# v10_microUSB.net
KiCad netlist of a schematic drawn in EAGLE
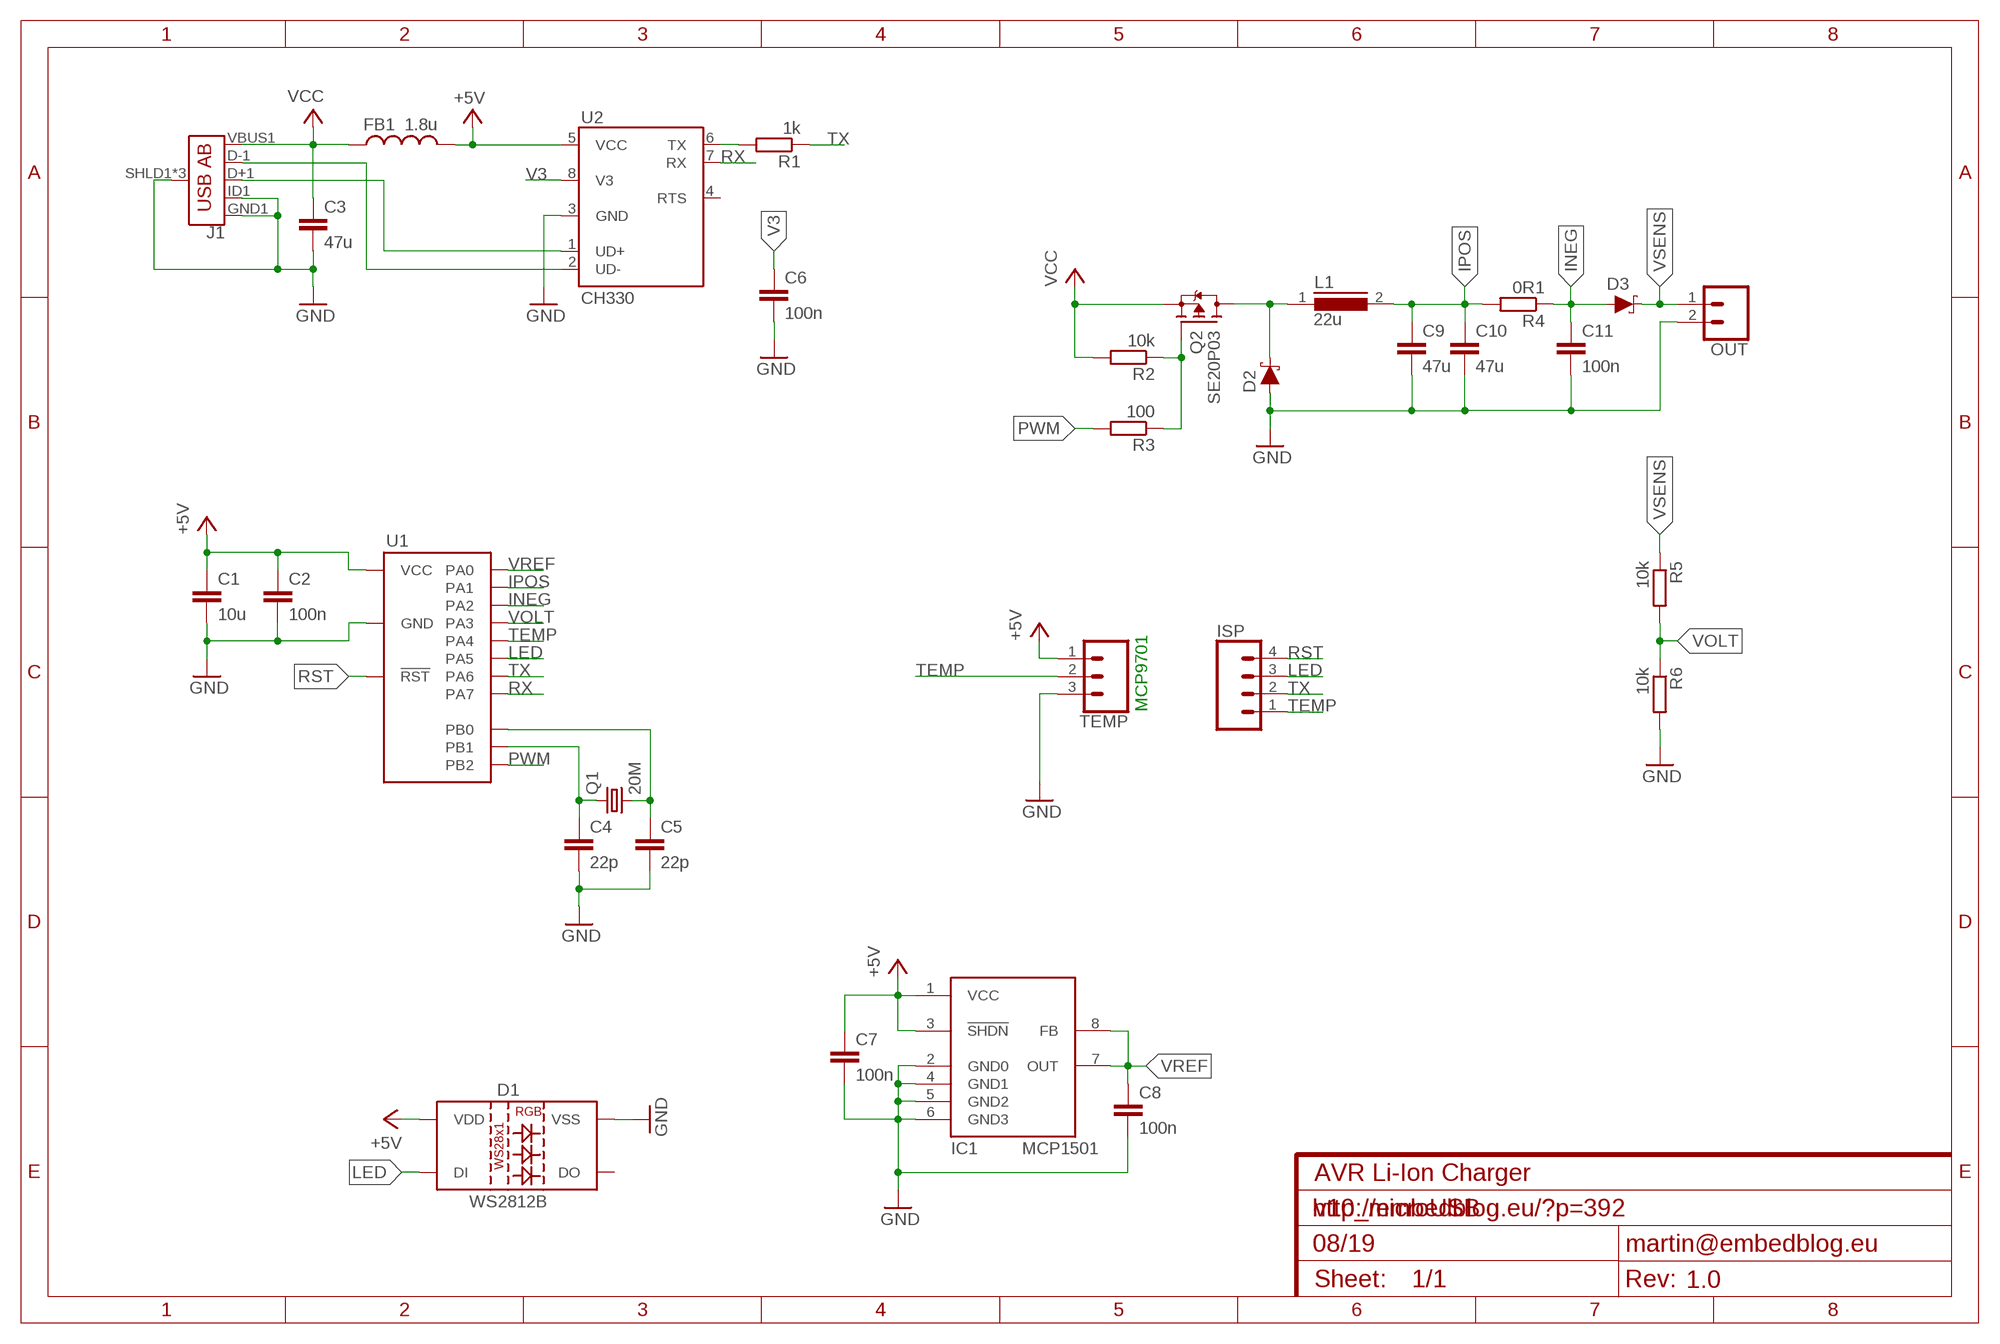
[diagram p0: schematic, sheet 1]

(export (version "E")
  (design (tool "Eeschema 10.0.6"))
  (components
    (comp (ref "C1")
      (value "10u")
      (footprint "eagle-import:C0805")
      (libsource (lib "eagle-import") (part "C-EUC0805"))
    )
    (comp (ref "C2")
      (value "100n")
      (footprint "eagle-import:C0805")
      (libsource (lib "eagle-import") (part "C-EUC0805"))
    )
    (comp (ref "C3")
      (value "47u")
      (footprint "eagle-import:C1206")
      (libsource (lib "eagle-import") (part "C-EUC1206"))
    )
    (comp (ref "C4")
      (value "22p")
      (footprint "eagle-import:C0805")
      (libsource (lib "eagle-import") (part "C-EUC0805"))
    )
    (comp (ref "C5")
      (value "22p")
      (footprint "eagle-import:C0805")
      (libsource (lib "eagle-import") (part "C-EUC0805"))
    )
    (comp (ref "C6")
      (value "100n")
      (footprint "eagle-import:C0805")
      (libsource (lib "eagle-import") (part "C-EUC0805"))
    )
    (comp (ref "C7")
      (value "100n")
      (footprint "eagle-import:C0805")
      (libsource (lib "eagle-import") (part "C-EUC0805"))
    )
    (comp (ref "C8")
      (value "100n")
      (footprint "eagle-import:C0805")
      (libsource (lib "eagle-import") (part "C-EUC0805"))
    )
    (comp (ref "C9")
      (value "47u")
      (footprint "eagle-import:C1206")
      (libsource (lib "eagle-import") (part "C-EUC1206"))
    )
    (comp (ref "C10")
      (value "47u")
      (footprint "eagle-import:C1206")
      (libsource (lib "eagle-import") (part "C-EUC1206"))
    )
    (comp (ref "C11")
      (value "100n")
      (footprint "eagle-import:C0805")
      (libsource (lib "eagle-import") (part "C-EUC0805"))
    )
    (comp (ref "D1")
      (value "WS2812B")
      (footprint "eagle-import:WS2812B")
      (libsource (lib "eagle-import") (part "WS2812B"))
    )
    (comp (ref "D2")
      (value "3A/40V/500mV")
      (footprint "eagle-import:SMA-DIODE")
      (libsource (lib "eagle-import") (part "DIODE-SCHOTTKY-B340A"))
    )
    (comp (ref "D3")
      (value "3A/40V/500mV")
      (footprint "eagle-import:SMA-DIODE")
      (libsource (lib "eagle-import") (part "DIODE-SCHOTTKY-B340A"))
    )
    (comp (ref "FB1")
      (value "1.8u")
      (footprint "eagle-import:1206")
      (libsource (lib "eagle-import") (part "FERRITE-BEADC"))
    )
    (comp (ref "IC1")
      (value "MCP1501")
      (footprint "eagle-import:SO08")
      (libsource (lib "eagle-import") (part "MCP1501"))
    )
    (comp (ref "ISP")
      (value "CONN_04")
      (footprint "eagle-import:1X04")
      (libsource (lib "eagle-import") (part "CONN_04"))
    )
    (comp (ref "J1")
      (value "USB_AB_SMT")
      (footprint "eagle-import:USB-AB-MICRO-SMD")
      (libsource (lib "eagle-import") (part "USB_AB_SMT"))
    )
    (comp (ref "L1")
      (value "22u")
      (footprint "eagle-import:DR73")
      (libsource (lib "eagle-import") (part "DR73"))
    )
    (comp (ref "OUT")
      (value "CONN_02PTH3")
      (footprint "eagle-import:1X02_LONGPADS")
      (libsource (lib "eagle-import") (part "CONN_02PTH3"))
    )
    (comp (ref "Q1")
      (value "20M")
      (footprint "eagle-import:HC49_S")
      (libsource (lib "eagle-import") (part "CRYSTALHC49S"))
    )
    (comp (ref "Q2")
      (value "SE20P03")
      (footprint "eagle-import:TO252")
      (libsource (lib "eagle-import") (part "FDD4141TO252"))
    )
    (comp (ref "R1")
      (value "1k")
      (footprint "eagle-import:R0805")
      (libsource (lib "eagle-import") (part "R-EU_R0805"))
    )
    (comp (ref "R2")
      (value "10k")
      (footprint "eagle-import:R0805")
      (libsource (lib "eagle-import") (part "R-EU_R0805"))
    )
    (comp (ref "R3")
      (value "100")
      (footprint "eagle-import:R0805")
      (libsource (lib "eagle-import") (part "R-EU_R0805"))
    )
    (comp (ref "R4")
      (value "0R1")
      (footprint "eagle-import:R1206")
      (libsource (lib "eagle-import") (part "R-EU_R1206"))
    )
    (comp (ref "R5")
      (value "10k")
      (footprint "eagle-import:R0805")
      (libsource (lib "eagle-import") (part "R-EU_R0805"))
    )
    (comp (ref "R6")
      (value "10k")
      (footprint "eagle-import:R0805")
      (libsource (lib "eagle-import") (part "R-EU_R0805"))
    )
    (comp (ref "TEMP")
      (value "455-1750-1-ND")
      (footprint "eagle-import:1X03")
      (libsource (lib "eagle-import") (part "CONN_03"))
    )
    (comp (ref "U1")
      (value "ATTINY24")
      (footprint "eagle-import:SO014")
      (libsource (lib "eagle-import") (part "ATTINY24"))
    )
    (comp (ref "U2")
      (value "CH330")
      (footprint "eagle-import:SO08")
      (libsource (lib "eagle-import") (part "CH330"))
    )
  )
  (nets
    (net (code "1") (name "+5V") (class "Default")
      (node (ref "C1") (pin "1") (pinfunction "1_1") (pintype "passive"))
      (node (ref "C2") (pin "1") (pinfunction "1_1") (pintype "passive"))
      (node (ref "C7") (pin "1") (pinfunction "1_1") (pintype "passive"))
      (node (ref "D1") (pin "1") (pinfunction "VDD_1") (pintype "bidirectional"))
      (node (ref "FB1") (pin "2") (pinfunction "2_2") (pintype "passive"))
      (node (ref "IC1") (pin "1") (pinfunction "VCC_1") (pintype "bidirectional"))
      (node (ref "IC1") (pin "3") (pinfunction "~{SHDN}_3") (pintype "bidirectional"))
      (node (ref "TEMP") (pin "1") (pinfunction "1_1") (pintype "passive"))
      (node (ref "U1") (pin "1") (pinfunction "VCC_1") (pintype "bidirectional"))
      (node (ref "U2") (pin "5") (pinfunction "VCC_5") (pintype "bidirectional"))
    )
    (net (code "2") (name "/RX") (class "Default")
      (node (ref "U1") (pin "6") (pinfunction "PA7_6") (pintype "bidirectional"))
      (node (ref "U2") (pin "7") (pinfunction "RX_7") (pintype "bidirectional"))
    )
    (net (code "3") (name "/TEMP") (class "Default")
      (node (ref "ISP") (pin "1") (pinfunction "1_1") (pintype "passive"))
      (node (ref "TEMP") (pin "2") (pinfunction "2_2") (pintype "passive"))
      (node (ref "U1") (pin "9") (pinfunction "PA4_9") (pintype "bidirectional"))
    )
    (net (code "4") (name "/TX") (class "Default")
      (node (ref "ISP") (pin "2") (pinfunction "2_2") (pintype "passive"))
      (node (ref "R1") (pin "1") (pinfunction "1_1") (pintype "passive"))
      (node (ref "U1") (pin "7") (pinfunction "PA6_7") (pintype "bidirectional"))
    )
    (net (code "5") (name "GND") (class "Default")
      (node (ref "C1") (pin "2") (pinfunction "2_2") (pintype "passive"))
      (node (ref "C10") (pin "2") (pinfunction "2_2") (pintype "passive"))
      (node (ref "C11") (pin "2") (pinfunction "2_2") (pintype "passive"))
      (node (ref "C2") (pin "2") (pinfunction "2_2") (pintype "passive"))
      (node (ref "C3") (pin "2") (pinfunction "2_2") (pintype "passive"))
      (node (ref "C4") (pin "2") (pinfunction "2_2") (pintype "passive"))
      (node (ref "C5") (pin "2") (pinfunction "2_2") (pintype "passive"))
      (node (ref "C6") (pin "2") (pinfunction "2_2") (pintype "passive"))
      (node (ref "C7") (pin "2") (pinfunction "2_2") (pintype "passive"))
      (node (ref "C8") (pin "2") (pinfunction "2_2") (pintype "passive"))
      (node (ref "C9") (pin "2") (pinfunction "2_2") (pintype "passive"))
      (node (ref "D1") (pin "3") (pinfunction "VSS_3") (pintype "bidirectional"))
      (node (ref "D2") (pin "A") (pinfunction "A_A") (pintype "passive"))
      (node (ref "IC1") (pin "2") (pinfunction "GND0_2") (pintype "bidirectional"))
      (node (ref "IC1") (pin "4") (pinfunction "GND1_4") (pintype "bidirectional"))
      (node (ref "IC1") (pin "5") (pinfunction "GND2_5") (pintype "bidirectional"))
      (node (ref "IC1") (pin "6") (pinfunction "GND3_6") (pintype "bidirectional"))
      (node (ref "J1") (pin "GND1") (pinfunction "GND_GND1") (pintype "power_in"))
      (node (ref "J1") (pin "ID1") (pinfunction "USBID_ID1") (pintype "bidirectional"))
      (node (ref "J1") (pin "SHLD1") (pinfunction "SHIELD_SHLD1") (pintype "bidirectional"))
      (node (ref "J1") (pin "SHLD2") (pinfunction "SHIELD_SHLD2") (pintype "bidirectional"))
      (node (ref "J1") (pin "SHLD3") (pinfunction "SHIELD_SHLD3") (pintype "bidirectional"))
      (node (ref "OUT") (pin "2") (pinfunction "2_2") (pintype "passive"))
      (node (ref "R6") (pin "2") (pinfunction "2_2") (pintype "passive"))
      (node (ref "TEMP") (pin "3") (pinfunction "3_3") (pintype "passive"))
      (node (ref "U1") (pin "14") (pinfunction "GND_14") (pintype "bidirectional"))
      (node (ref "U2") (pin "3") (pinfunction "GND_3") (pintype "bidirectional"))
    )
    (net (code "6") (name "INEG") (class "Default")
      (node (ref "C11") (pin "1") (pinfunction "1_1") (pintype "passive"))
      (node (ref "D3") (pin "A") (pinfunction "A_A") (pintype "passive"))
      (node (ref "R4") (pin "1") (pinfunction "1_1") (pintype "passive"))
      (node (ref "U1") (pin "11") (pinfunction "PA2_11") (pintype "bidirectional"))
    )
    (net (code "7") (name "IPOS") (class "Default")
      (node (ref "C10") (pin "1") (pinfunction "1_1") (pintype "passive"))
      (node (ref "C9") (pin "1") (pinfunction "1_1") (pintype "passive"))
      (node (ref "L1") (pin "2") (pinfunction "2_2") (pintype "passive"))
      (node (ref "R4") (pin "2") (pinfunction "2_2") (pintype "passive"))
      (node (ref "U1") (pin "12") (pinfunction "PA1_12") (pintype "bidirectional"))
    )
    (net (code "8") (name "LED") (class "Default")
      (node (ref "D1") (pin "4") (pinfunction "DI_4") (pintype "bidirectional"))
      (node (ref "ISP") (pin "3") (pinfunction "3_3") (pintype "passive"))
      (node (ref "U1") (pin "8") (pinfunction "PA5_8") (pintype "bidirectional"))
    )
    (net (code "9") (name "Net-(J1-D+)") (class "Default")
      (node (ref "J1") (pin "D+1") (pinfunction "D+_D+1") (pintype "bidirectional"))
      (node (ref "U2") (pin "1") (pinfunction "UD+_1") (pintype "bidirectional"))
    )
    (net (code "10") (name "Net-(J1-D-)") (class "Default")
      (node (ref "J1") (pin "D-1") (pinfunction "D-_D-1") (pintype "bidirectional"))
      (node (ref "U2") (pin "2") (pinfunction "UD-_2") (pintype "bidirectional"))
    )
    (net (code "11") (name "Net-(Q2-D)") (class "Default")
      (node (ref "D2") (pin "C") (pinfunction "C_C") (pintype "passive"))
      (node (ref "L1") (pin "1") (pinfunction "1_1") (pintype "passive"))
      (node (ref "Q2") (pin "3") (pinfunction "D_3") (pintype "passive"))
    )
    (net (code "12") (name "Net-(Q2-G)") (class "Default")
      (node (ref "Q2") (pin "1") (pinfunction "G_1") (pintype "passive"))
      (node (ref "R2") (pin "1") (pinfunction "1_1") (pintype "passive"))
      (node (ref "R3") (pin "1") (pinfunction "1_1") (pintype "passive"))
    )
    (net (code "13") (name "Net-(U1-PB0)") (class "Default")
      (node (ref "C5") (pin "1") (pinfunction "1_1") (pintype "passive"))
      (node (ref "Q1") (pin "2") (pinfunction "2_2") (pintype "passive"))
      (node (ref "U1") (pin "2") (pinfunction "PB0_2") (pintype "bidirectional"))
    )
    (net (code "14") (name "Net-(U1-PB1)") (class "Default")
      (node (ref "C4") (pin "1") (pinfunction "1_1") (pintype "passive"))
      (node (ref "Q1") (pin "1") (pinfunction "1_1") (pintype "passive"))
      (node (ref "U1") (pin "3") (pinfunction "PB1_3") (pintype "bidirectional"))
    )
    (net (code "15") (name "Net-(U2-TX)") (class "Default")
      (node (ref "R1") (pin "2") (pinfunction "2_2") (pintype "passive"))
      (node (ref "U2") (pin "6") (pinfunction "TX_6") (pintype "bidirectional"))
    )
    (net (code "16") (name "PWM") (class "Default")
      (node (ref "R3") (pin "2") (pinfunction "2_2") (pintype "passive"))
      (node (ref "U1") (pin "5") (pinfunction "PB2_5") (pintype "bidirectional"))
    )
    (net (code "17") (name "RST") (class "Default")
      (node (ref "ISP") (pin "4") (pinfunction "4_4") (pintype "passive"))
      (node (ref "U1") (pin "4") (pinfunction "~{RST}_4") (pintype "bidirectional"))
    )
    (net (code "18") (name "V3") (class "Default")
      (node (ref "C6") (pin "1") (pinfunction "1_1") (pintype "passive"))
      (node (ref "U2") (pin "8") (pinfunction "V3_8") (pintype "bidirectional"))
    )
    (net (code "19") (name "VCC") (class "Default")
      (node (ref "C3") (pin "1") (pinfunction "1_1") (pintype "passive"))
      (node (ref "FB1") (pin "1") (pinfunction "1_1") (pintype "passive"))
      (node (ref "J1") (pin "VBUS1") (pinfunction "VBUS_VBUS1") (pintype "power_in"))
      (node (ref "Q2") (pin "2") (pinfunction "S_2") (pintype "passive"))
      (node (ref "R2") (pin "2") (pinfunction "2_2") (pintype "passive"))
    )
    (net (code "20") (name "VOLT") (class "Default")
      (node (ref "R5") (pin "2") (pinfunction "2_2") (pintype "passive"))
      (node (ref "R6") (pin "1") (pinfunction "1_1") (pintype "passive"))
      (node (ref "U1") (pin "10") (pinfunction "PA3_10") (pintype "bidirectional"))
    )
    (net (code "21") (name "VREF") (class "Default")
      (node (ref "C8") (pin "1") (pinfunction "1_1") (pintype "passive"))
      (node (ref "IC1") (pin "7") (pinfunction "OUT_7") (pintype "bidirectional"))
      (node (ref "IC1") (pin "8") (pinfunction "FB_8") (pintype "bidirectional"))
      (node (ref "U1") (pin "13") (pinfunction "PA0_13") (pintype "bidirectional"))
    )
    (net (code "22") (name "VSENS") (class "Default")
      (node (ref "D3") (pin "C") (pinfunction "C_C") (pintype "passive"))
      (node (ref "OUT") (pin "1") (pinfunction "1_1") (pintype "passive"))
      (node (ref "R5") (pin "1") (pinfunction "1_1") (pintype "passive"))
    )
    (net (code "23") (name "unconnected-(D1-DO-Pad2)") (class "Default")
      (node (ref "D1") (pin "2") (pinfunction "DO_2") (pintype "bidirectional"))
    )
    (net (code "24") (name "unconnected-(U2-RTS-Pad4)") (class "Default")
      (node (ref "U2") (pin "4") (pinfunction "RTS_4") (pintype "bidirectional"))
    )
  )
)
